# V1_4.net
KiCad netlist of a schematic drawn in Altium Designer
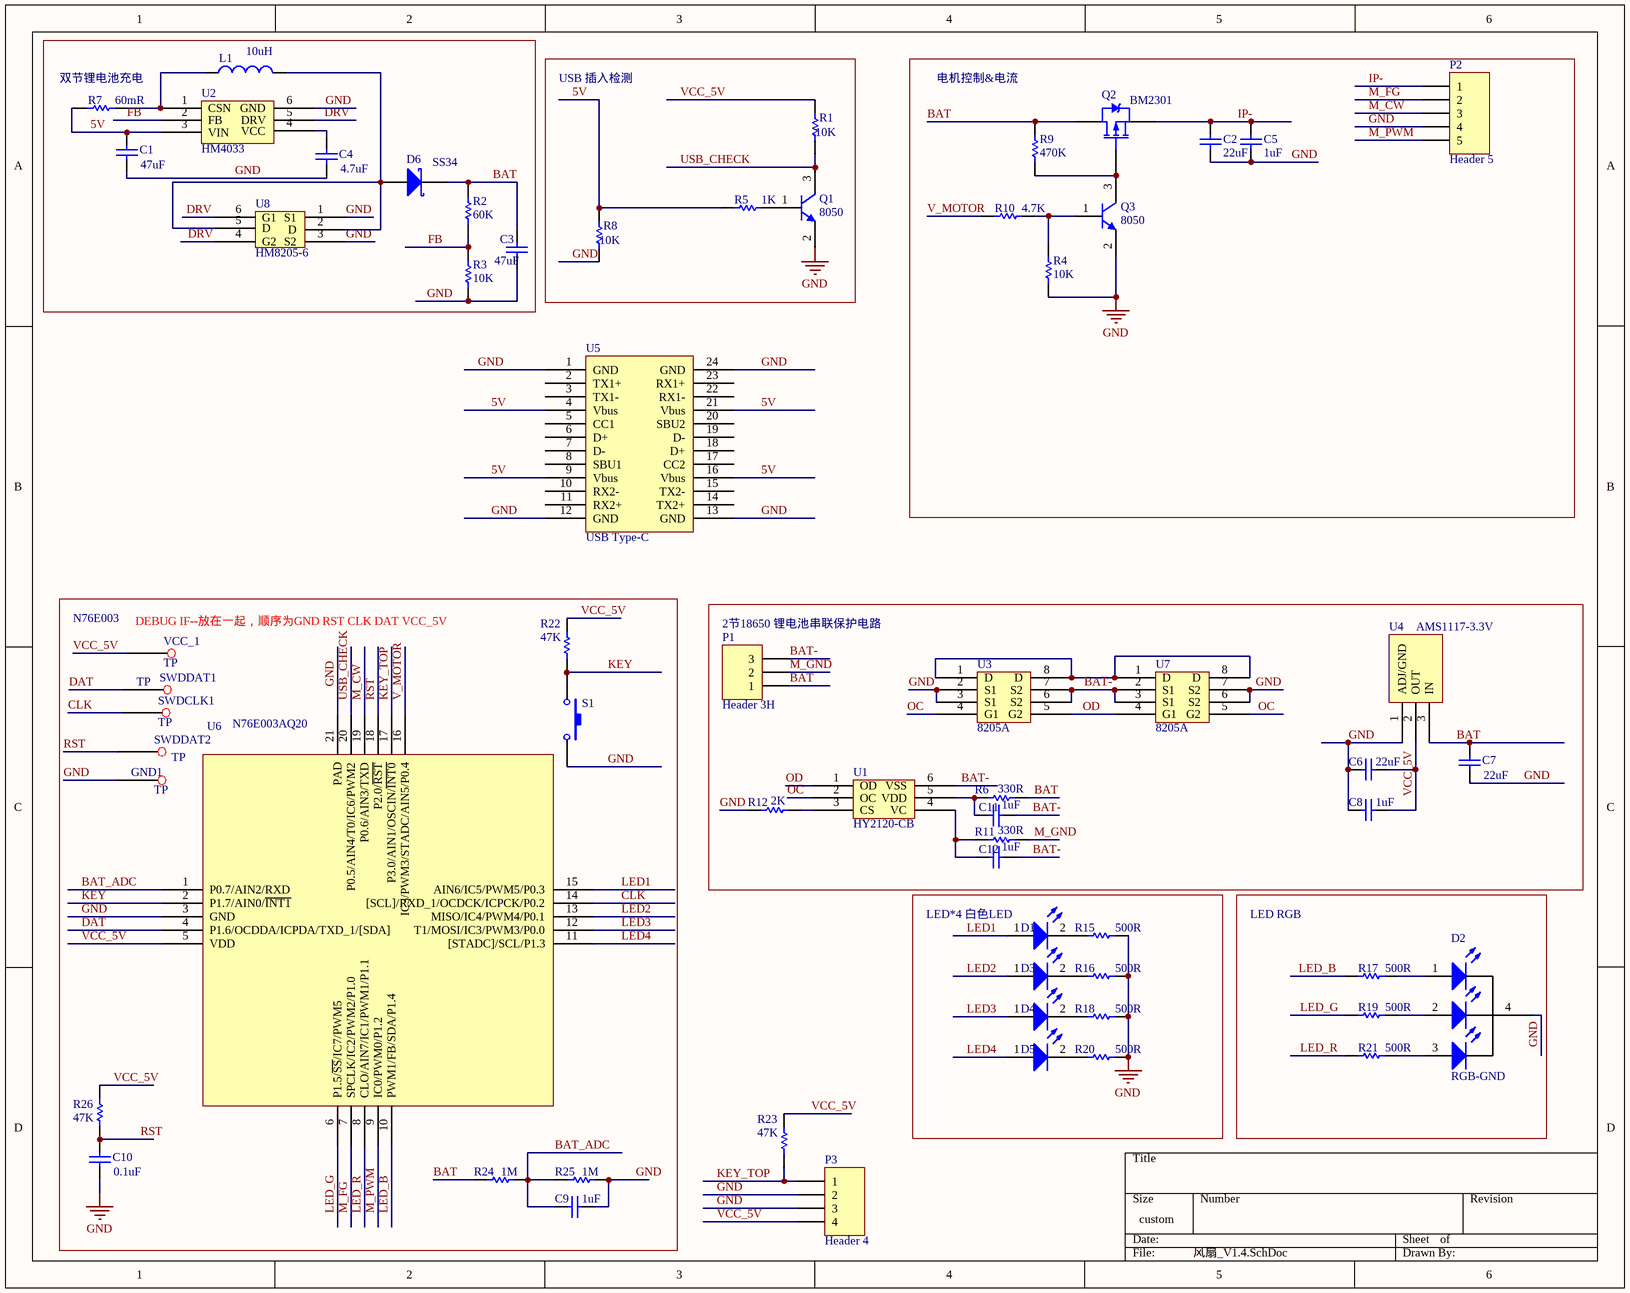
[diagram p0: 风扇_V1.4.SchDoc]

(export (version "E")
  (design (tool "Eeschema 10.0.6"))
  (components
    (comp (ref "C1")
      (value "47uF")
      (footprint "C-0603")
      (description "Capacitor")
      (fields (field (name "PUBLISHER") "Altium Limited"))
      (libsource (lib "Miscellaneous Devices") (part "Cap"))
    )
    (comp (ref "C2")
      (value "22uF")
      (footprint "C-0603")
      (description "Capacitor")
      (fields (field (name "PUBLISHER") "Altium Limited"))
      (libsource (lib "Miscellaneous Devices") (part "Cap"))
    )
    (comp (ref "C3")
      (value "47uF")
      (footprint "C-0603")
      (description "Capacitor")
      (fields (field (name "PUBLISHER") "Altium Limited"))
      (libsource (lib "Miscellaneous Devices") (part "Cap"))
    )
    (comp (ref "C4")
      (value "4.7uF")
      (footprint "C-0402")
      (description "Capacitor")
      (fields (field (name "PUBLISHER") "Altium Limited"))
      (libsource (lib "Miscellaneous Devices") (part "Cap"))
    )
    (comp (ref "C5")
      (value "1uF")
      (footprint "C-0402")
      (description "Capacitor")
      (fields (field (name "PUBLISHER") "Altium Limited"))
      (libsource (lib "Miscellaneous Devices") (part "Cap"))
    )
    (comp (ref "C6")
      (value "22uF")
      (footprint "C-0603")
      (description "Capacitor")
      (fields (field (name "PUBLISHER") "Altium Limited"))
      (libsource (lib "Miscellaneous Devices") (part "Cap"))
    )
    (comp (ref "C7")
      (value "22uF")
      (footprint "C-0603")
      (description "Capacitor")
      (fields (field (name "PUBLISHER") "Altium Limited"))
      (libsource (lib "Miscellaneous Devices") (part "Cap"))
    )
    (comp (ref "C8")
      (value "1uF")
      (footprint "C-0402")
      (description "Capacitor")
      (fields (field (name "PUBLISHER") "Altium Limited"))
      (libsource (lib "Miscellaneous Devices") (part "Cap"))
    )
    (comp (ref "C9")
      (value "1uF")
      (footprint "C-0402")
      (description "Capacitor")
      (fields (field (name "PUBLISHER") "Altium Limited"))
      (libsource (lib "Miscellaneous Devices") (part "Cap"))
    )
    (comp (ref "C10")
      (value "0.1uF")
      (footprint "C-0402")
      (description "Capacitor")
      (fields (field (name "PUBLISHER") "Altium Limited"))
      (libsource (lib "Miscellaneous Devices") (part "Cap"))
    )
    (comp (ref "C11")
      (value "1uF")
      (footprint "C-0402")
      (description "Capacitor")
      (fields (field (name "PUBLISHER") "Altium Limited"))
      (libsource (lib "Miscellaneous Devices") (part "Cap"))
    )
    (comp (ref "C12")
      (value "1uF")
      (footprint "C-0402")
      (description "Capacitor")
      (fields (field (name "PUBLISHER") "Altium Limited"))
      (libsource (lib "Miscellaneous Devices") (part "Cap"))
    )
    (comp (ref "D1")
      (value "LED0")
      (footprint "LED-0603")
      (description "Typical INFRARED GaAs LED")
      (fields (field (name "PUBLISHER") "Altium Limited"))
      (libsource (lib "Miscellaneous Devices") (part "LED0"))
    )
    (comp (ref "D2")
      (value "RGB-GND")
      (footprint "0603*2-LED")
      (libsource (lib "Others_IC_SCH_LIB") (part "RGB-GND"))
    )
    (comp (ref "D3")
      (value "LED0")
      (footprint "LED-0603")
      (description "Typical INFRARED GaAs LED")
      (fields (field (name "PUBLISHER") "Altium Limited"))
      (libsource (lib "Miscellaneous Devices") (part "LED0"))
    )
    (comp (ref "D4")
      (value "LED0")
      (footprint "LED-0603")
      (description "Typical INFRARED GaAs LED")
      (fields (field (name "PUBLISHER") "Altium Limited"))
      (libsource (lib "Miscellaneous Devices") (part "LED0"))
    )
    (comp (ref "D5")
      (value "LED0")
      (footprint "LED-0603")
      (description "Typical INFRARED GaAs LED")
      (fields (field (name "PUBLISHER") "Altium Limited"))
      (libsource (lib "Miscellaneous Devices") (part "LED0"))
    )
    (comp (ref "D6")
      (value "SS34")
      (footprint "HM4033 V1.0:DSMD")
      (description "Schottky Rectifier")
      (fields (field (name "PUBLISHER") "Altium Limited"))
      (libsource (lib "Miscellaneous Devices") (part "Diode 10TQ035"))
    )
    (comp (ref "GND1") (value "TP") (footprint "TP-1.5") (libsource (lib "Others_IC_SCH_LIB") (part "TP")))
    (comp (ref "L1")
      (value "10uH")
      (footprint "L-SMD")
      (description "Inductor")
      (fields (field (name "PUBLISHER") "Altium Limited"))
      (libsource (lib "Miscellaneous Devices") (part "Inductor"))
    )
    (comp (ref "P1")
      (value "Header 3H")
      (footprint "HED1X3")
      (description "Header, 3-Pin, Right Angle")
      (fields (field (name "PUBLISHER") "Altium Limited"))
      (libsource (lib "Miscellaneous Connectors") (part "Header 3H"))
    )
    (comp (ref "P2")
      (value "Header 5")
      (footprint "HDR1X5")
      (description "Header, 5-Pin")
      (fields (field (name "PUBLISHER") "Altium Limited"))
      (libsource (lib "Miscellaneous Connectors") (part "Header 5"))
    )
    (comp (ref "P3")
      (value "Header 4")
      (footprint "HDR1X4")
      (description "Header, 4-Pin")
      (fields (field (name "PUBLISHER") "Altium Limited"))
      (libsource (lib "Miscellaneous Connectors") (part "Header 4"))
    )
    (comp (ref "Q1")
      (value "8050")
      (footprint "SOT-23")
      (description "NPN Bipolar Transistor")
      (fields (field (name "PUBLISHER") "Altium Limited"))
      (libsource (lib "Miscellaneous Devices") (part "NPN"))
    )
    (comp (ref "Q2")
      (value "BM2301")
      (footprint "SOT-23")
      (description "P-Channel Power MOSFET")
      (fields (field (name "PUBLISHER") "Altium Limited"))
      (libsource (lib "Miscellaneous Devices") (part "PMOS-2"))
    )
    (comp (ref "Q3")
      (value "8050")
      (footprint "SOT-23")
      (description "NPN Bipolar Transistor")
      (fields (field (name "PUBLISHER") "Altium Limited"))
      (libsource (lib "Miscellaneous Devices") (part "NPN"))
    )
    (comp (ref "R1")
      (value "10K")
      (footprint "R-0402")
      (description "Resistor")
      (fields (field (name "PUBLISHER") "Altium Limited"))
      (libsource (lib "Miscellaneous Devices") (part "Res1"))
    )
    (comp (ref "R2")
      (value "60K")
      (footprint "R-0402")
      (description "Resistor")
      (fields (field (name "PUBLISHER") "Altium Limited"))
      (libsource (lib "Miscellaneous Devices") (part "Res1"))
    )
    (comp (ref "R3")
      (value "10K")
      (footprint "R-0402")
      (description "Resistor")
      (fields (field (name "PUBLISHER") "Altium Limited"))
      (libsource (lib "Miscellaneous Devices") (part "Res1"))
    )
    (comp (ref "R4")
      (value "10K")
      (footprint "R-0402")
      (description "Resistor")
      (fields (field (name "PUBLISHER") "Altium Limited"))
      (libsource (lib "Miscellaneous Devices") (part "Res1"))
    )
    (comp (ref "R5")
      (value "1K")
      (footprint "R-0402")
      (description "Resistor")
      (fields (field (name "PUBLISHER") "Altium Limited"))
      (libsource (lib "Miscellaneous Devices") (part "Res1"))
    )
    (comp (ref "R6")
      (value "330R")
      (footprint "R-0402")
      (description "Resistor")
      (fields (field (name "PUBLISHER") "Altium Limited"))
      (libsource (lib "Miscellaneous Devices") (part "Res1"))
    )
    (comp (ref "R7")
      (value "60mR")
      (footprint "R-0402")
      (description "Resistor")
      (fields (field (name "PUBLISHER") "Altium Limited"))
      (libsource (lib "Miscellaneous Devices") (part "Res1"))
    )
    (comp (ref "R8")
      (value "10K")
      (footprint "R-0402")
      (description "Resistor")
      (fields (field (name "PUBLISHER") "Altium Limited"))
      (libsource (lib "Miscellaneous Devices") (part "Res1"))
    )
    (comp (ref "R9")
      (value "470K")
      (footprint "R-0402")
      (description "Resistor")
      (fields (field (name "PUBLISHER") "Altium Limited"))
      (libsource (lib "Miscellaneous Devices") (part "Res1"))
    )
    (comp (ref "R10")
      (value "4.7K")
      (footprint "R-0402")
      (description "Resistor")
      (fields (field (name "PUBLISHER") "Altium Limited"))
      (libsource (lib "Miscellaneous Devices") (part "Res1"))
    )
    (comp (ref "R11")
      (value "330R")
      (footprint "R-0402")
      (description "Resistor")
      (fields (field (name "PUBLISHER") "Altium Limited"))
      (libsource (lib "Miscellaneous Devices") (part "Res1"))
    )
    (comp (ref "R12")
      (value "2K")
      (footprint "R-0402")
      (description "Resistor")
      (fields (field (name "PUBLISHER") "Altium Limited"))
      (libsource (lib "Miscellaneous Devices") (part "Res1"))
    )
    (comp (ref "R15")
      (value "500R")
      (footprint "R-0402")
      (description "Resistor")
      (fields (field (name "PUBLISHER") "Altium Limited"))
      (libsource (lib "Miscellaneous Devices") (part "Res1"))
    )
    (comp (ref "R16")
      (value "500R")
      (footprint "R-0402")
      (description "Resistor")
      (fields (field (name "PUBLISHER") "Altium Limited"))
      (libsource (lib "Miscellaneous Devices") (part "Res1"))
    )
    (comp (ref "R17")
      (value "500R")
      (footprint "R-0402")
      (description "Resistor")
      (fields (field (name "PUBLISHER") "Altium Limited"))
      (libsource (lib "Miscellaneous Devices") (part "Res1"))
    )
    (comp (ref "R18")
      (value "500R")
      (footprint "R-0402")
      (description "Resistor")
      (fields (field (name "PUBLISHER") "Altium Limited"))
      (libsource (lib "Miscellaneous Devices") (part "Res1"))
    )
    (comp (ref "R19")
      (value "500R")
      (footprint "R-0402")
      (description "Resistor")
      (fields (field (name "PUBLISHER") "Altium Limited"))
      (libsource (lib "Miscellaneous Devices") (part "Res1"))
    )
    (comp (ref "R20")
      (value "500R")
      (footprint "R-0402")
      (description "Resistor")
      (fields (field (name "PUBLISHER") "Altium Limited"))
      (libsource (lib "Miscellaneous Devices") (part "Res1"))
    )
    (comp (ref "R21")
      (value "500R")
      (footprint "R-0402")
      (description "Resistor")
      (fields (field (name "PUBLISHER") "Altium Limited"))
      (libsource (lib "Miscellaneous Devices") (part "Res1"))
    )
    (comp (ref "R22")
      (value "47K")
      (footprint "R-0402")
      (description "Resistor")
      (fields (field (name "PUBLISHER") "Altium Limited"))
      (libsource (lib "Miscellaneous Devices") (part "Res1"))
    )
    (comp (ref "R23")
      (value "47K")
      (footprint "R-0402")
      (description "Resistor")
      (fields (field (name "PUBLISHER") "Altium Limited"))
      (libsource (lib "Miscellaneous Devices") (part "Res1"))
    )
    (comp (ref "R24")
      (value "1M")
      (footprint "R-0402")
      (description "Resistor")
      (fields (field (name "PUBLISHER") "Altium Limited"))
      (libsource (lib "Miscellaneous Devices") (part "Res1"))
    )
    (comp (ref "R25")
      (value "1M")
      (footprint "R-0402")
      (description "Resistor")
      (fields (field (name "PUBLISHER") "Altium Limited"))
      (libsource (lib "Miscellaneous Devices") (part "Res1"))
    )
    (comp (ref "R26")
      (value "47K")
      (footprint "R-0402")
      (description "Resistor")
      (fields (field (name "PUBLISHER") "Altium Limited"))
      (libsource (lib "Miscellaneous Devices") (part "Res1"))
    )
    (comp (ref "S1")
      (value "SW-PB")
      (footprint "SW-6*6*4.3")
      (description "Switch")
      (fields (field (name "PUBLISHER") "Altium Limited"))
      (libsource (lib "Miscellaneous Devices") (part "SW-PB"))
    )
    (comp (ref "SWDCLK1") (value "TP") (footprint "TP-1.5") (libsource (lib "Others_IC_SCH_LIB") (part "TP")))
    (comp (ref "SWDDAT1") (value "TP") (footprint "TP-1.5") (libsource (lib "Others_IC_SCH_LIB") (part "TP")))
    (comp (ref "SWDDAT2") (value "TP") (footprint "TP-1.5") (libsource (lib "Others_IC_SCH_LIB") (part "TP")))
    (comp (ref "U1")
      (value "HY2120-CB")
      (footprint "SOT-23-6L")
      (libsource (lib "Others_IC_SCH_LIB") (part "HY2120"))
    )
    (comp (ref "U2")
      (value "HM4033")
      (footprint "SOT-23-6L")
      (libsource (lib "Others_IC_SCH_LIB") (part "HM4033"))
    )
    (comp (ref "U3")
      (value "8205A")
      (footprint "TSSOP8")
      (libsource (lib "Others_IC_SCH_LIB") (part "8205A"))
    )
    (comp (ref "U4")
      (value "AMS1117-3.3V")
      (footprint "SOT-223")
      (libsource (lib "Others_IC_SCH_LIB") (part "AMS1117"))
    )
    (comp (ref "U5")
      (value "USB Type-C")
      (footprint "USB-type C")
      (libsource (lib "Others_IC_SCH_LIB") (part "USB Type-C"))
    )
    (comp (ref "U6")
      (value "N76E003AQ20")
      (footprint "QFN-20 0.4mm")
      (libsource (lib "Others_IC_SCH_LIB") (part "N76E003AQ20"))
    )
    (comp (ref "U7")
      (value "8205A")
      (footprint "TSSOP8")
      (libsource (lib "Others_IC_SCH_LIB") (part "8205A"))
    )
    (comp (ref "U8")
      (value "HM8205-6")
      (footprint "SOT-23-6L")
      (libsource (lib "Others_IC_SCH_LIB") (part "HM8205-6"))
    )
    (comp (ref "VCC_1") (value "TP") (footprint "TP-1.5") (libsource (lib "Others_IC_SCH_LIB") (part "TP")))
  )
  (nets
    (net (code "1") (name "/5V") (class "Default")
      (node (ref "C1") (pin "1") (pinfunction "1_1") (pintype "passive"))
      (node (ref "R5") (pin "1") (pinfunction "1_1") (pintype "passive"))
      (node (ref "R7") (pin "2") (pinfunction "2_2") (pintype "passive"))
      (node (ref "R8") (pin "1") (pinfunction "1_1") (pintype "passive"))
      (node (ref "U2") (pin "3") (pinfunction "VIN_3") (pintype "passive"))
      (node (ref "U5") (pin "16") (pinfunction "Vbus_16") (pintype "passive"))
      (node (ref "U5") (pin "21") (pinfunction "Vbus_21") (pintype "passive"))
      (node (ref "U5") (pin "4") (pinfunction "Vbus_4") (pintype "passive"))
      (node (ref "U5") (pin "9") (pinfunction "Vbus_9") (pintype "passive"))
    )
    (net (code "2") (name "/BAT") (class "Default")
      (node (ref "C3") (pin "2") (pinfunction "2_2") (pintype "passive"))
      (node (ref "C7") (pin "2") (pinfunction "2_2") (pintype "passive"))
      (node (ref "D6") (pin "1") (pinfunction "K_1") (pintype "passive"))
      (node (ref "P1") (pin "1") (pinfunction "1_1") (pintype "passive"))
      (node (ref "Q2") (pin "2") (pinfunction "D_2") (pintype "passive"))
      (node (ref "R2") (pin "1") (pinfunction "1_1") (pintype "passive"))
      (node (ref "R24") (pin "1") (pinfunction "1_1") (pintype "passive"))
      (node (ref "R6") (pin "2") (pinfunction "2_2") (pintype "passive"))
      (node (ref "R9") (pin "2") (pinfunction "2_2") (pintype "passive"))
      (node (ref "U4") (pin "3") (pinfunction "IN_3") (pintype "passive"))
    )
    (net (code "3") (name "/BAT-") (class "Default")
      (node (ref "C11") (pin "1") (pinfunction "1_1") (pintype "passive"))
      (node (ref "C12") (pin "1") (pinfunction "1_1") (pintype "passive"))
      (node (ref "P1") (pin "3") (pinfunction "3_3") (pintype "passive"))
      (node (ref "U1") (pin "6") (pinfunction "VSS_6") (pintype "passive"))
      (node (ref "U3") (pin "6") (pinfunction "S2_6") (pintype "passive"))
      (node (ref "U3") (pin "7") (pinfunction "S2_7") (pintype "passive"))
      (node (ref "U7") (pin "2") (pinfunction "S1_2") (pintype "passive"))
      (node (ref "U7") (pin "3") (pinfunction "S1_3") (pintype "passive"))
    )
    (net (code "4") (name "/BAT_ADC") (class "Default")
      (node (ref "C9") (pin "2") (pinfunction "2_2") (pintype "passive"))
      (node (ref "R24") (pin "2") (pinfunction "2_2") (pintype "passive"))
      (node (ref "R25") (pin "1") (pinfunction "1_1") (pintype "passive"))
      (node (ref "U6") (pin "1") (pinfunction "P0.7/AIN2/RXD_1") (pintype "passive"))
    )
    (net (code "5") (name "/CLK") (class "Default")
      (node (ref "SWDCLK1") (pin "1") (pinfunction "1_1") (pintype "passive"))
      (node (ref "U6") (pin "14") (pinfunction "[SCL]/RXD_1/OCDCK/ICPCK/P0.2_14") (pintype "passive"))
    )
    (net (code "6") (name "/DAT") (class "Default")
      (node (ref "SWDDAT1") (pin "1") (pinfunction "1_1") (pintype "passive"))
      (node (ref "U6") (pin "4") (pinfunction "P1.6/OCDDA/ICPDA/TXD_1/[SDA]_4") (pintype "passive"))
    )
    (net (code "7") (name "/DRV") (class "Default")
      (node (ref "U2") (pin "5") (pinfunction "DRV_5") (pintype "passive"))
      (node (ref "U8") (pin "4") (pinfunction "G2_4") (pintype "passive"))
      (node (ref "U8") (pin "6") (pinfunction "G1_6") (pintype "passive"))
    )
    (net (code "8") (name "/FB") (class "Default")
      (node (ref "R2") (pin "2") (pinfunction "2_2") (pintype "passive"))
      (node (ref "R3") (pin "1") (pinfunction "1_1") (pintype "passive"))
      (node (ref "U2") (pin "2") (pinfunction "FB_2") (pintype "passive"))
    )
    (net (code "9") (name "/IP-") (class "Default")
      (node (ref "C2") (pin "2") (pinfunction "2_2") (pintype "passive"))
      (node (ref "C5") (pin "2") (pinfunction "2_2") (pintype "passive"))
      (node (ref "P2") (pin "1") (pinfunction "1_1") (pintype "passive"))
      (node (ref "Q2") (pin "3") (pinfunction "S_3") (pintype "passive"))
    )
    (net (code "10") (name "/KEY") (class "Default")
      (node (ref "R22") (pin "1") (pinfunction "1_1") (pintype "passive"))
      (node (ref "S1") (pin "1") (pinfunction "1_1") (pintype "passive"))
      (node (ref "U6") (pin "2") (pinfunction "P1.7/AIN0/~{INT1}_2") (pintype "passive"))
    )
    (net (code "11") (name "/KEY_TOP") (class "Default")
      (node (ref "P3") (pin "1") (pinfunction "1_1") (pintype "passive"))
      (node (ref "R23") (pin "1") (pinfunction "1_1") (pintype "passive"))
      (node (ref "U6") (pin "17") (pinfunction "P3.0/AIN1/OSCIN/~{INT0}_17") (pintype "passive"))
    )
    (net (code "12") (name "/LED1") (class "Default")
      (node (ref "D1") (pin "1") (pinfunction "A_1") (pintype "passive"))
      (node (ref "U6") (pin "15") (pinfunction "AIN6/IC5/PWM5/P0.3_15") (pintype "passive"))
    )
    (net (code "13") (name "/LED2") (class "Default")
      (node (ref "D3") (pin "1") (pinfunction "A_1") (pintype "passive"))
      (node (ref "U6") (pin "13") (pinfunction "MISO/IC4/PWM4/P0.1_13") (pintype "passive"))
    )
    (net (code "14") (name "/LED3") (class "Default")
      (node (ref "D4") (pin "1") (pinfunction "A_1") (pintype "passive"))
      (node (ref "U6") (pin "12") (pinfunction "T1/MOSI/IC3/PWM3/P0.0_12") (pintype "passive"))
    )
    (net (code "15") (name "/LED4") (class "Default")
      (node (ref "D5") (pin "1") (pinfunction "A_1") (pintype "passive"))
      (node (ref "U6") (pin "11") (pinfunction "[STADC]/SCL/P1.3_11") (pintype "passive"))
    )
    (net (code "16") (name "/LED_B") (class "Default")
      (node (ref "R17") (pin "1") (pinfunction "1_1") (pintype "passive"))
      (node (ref "U6") (pin "10") (pinfunction "PWM1/FB/SDA/P1.4_10") (pintype "passive"))
    )
    (net (code "17") (name "/LED_G") (class "Default")
      (node (ref "R19") (pin "1") (pinfunction "1_1") (pintype "passive"))
      (node (ref "U6") (pin "6") (pinfunction "P1.5/~{SS}/IC7/PWM5_6") (pintype "passive"))
    )
    (net (code "18") (name "/LED_R") (class "Default")
      (node (ref "R21") (pin "1") (pinfunction "1_1") (pintype "passive"))
      (node (ref "U6") (pin "8") (pinfunction "CLO/AIN7/IC1/PWM1/P1.1_8") (pintype "passive"))
    )
    (net (code "19") (name "/M_CW") (class "Default")
      (node (ref "P2") (pin "3") (pinfunction "3_3") (pintype "passive"))
      (node (ref "U6") (pin "19") (pinfunction "P0.6/AIN3/TXD_19") (pintype "passive"))
    )
    (net (code "20") (name "/M_FG") (class "Default")
      (node (ref "P2") (pin "2") (pinfunction "2_2") (pintype "passive"))
      (node (ref "U6") (pin "7") (pinfunction "SPCLK/IC2/PWM2/P1.0_7") (pintype "passive"))
    )
    (net (code "21") (name "/M_GND") (class "Default")
      (node (ref "P1") (pin "2") (pinfunction "2_2") (pintype "passive"))
      (node (ref "R11") (pin "2") (pinfunction "2_2") (pintype "passive"))
    )
    (net (code "22") (name "/M_PWM") (class "Default")
      (node (ref "P2") (pin "5") (pinfunction "5_5") (pintype "passive"))
      (node (ref "U6") (pin "9") (pinfunction "IC0/PWM0/P1.2_9") (pintype "passive"))
    )
    (net (code "23") (name "/OC") (class "Default")
      (node (ref "U1") (pin "2") (pinfunction "OC_2") (pintype "passive"))
      (node (ref "U3") (pin "4") (pinfunction "G1_4") (pintype "passive"))
      (node (ref "U7") (pin "5") (pinfunction "G2_5") (pintype "passive"))
    )
    (net (code "24") (name "/OD") (class "Default")
      (node (ref "U1") (pin "1") (pinfunction "OD_1") (pintype "passive"))
      (node (ref "U3") (pin "5") (pinfunction "G2_5") (pintype "passive"))
      (node (ref "U7") (pin "4") (pinfunction "G1_4") (pintype "passive"))
    )
    (net (code "25") (name "/RST") (class "Default")
      (node (ref "C10") (pin "2") (pinfunction "2_2") (pintype "passive"))
      (node (ref "R26") (pin "1") (pinfunction "1_1") (pintype "passive"))
      (node (ref "SWDDAT2") (pin "1") (pinfunction "1_1") (pintype "passive"))
      (node (ref "U6") (pin "18") (pinfunction "P2.0/~{RST}_18") (pintype "passive"))
    )
    (net (code "26") (name "/USB_CHECK") (class "Default")
      (node (ref "Q1") (pin "3") (pinfunction "C_3") (pintype "passive"))
      (node (ref "R1") (pin "1") (pinfunction "1_1") (pintype "passive"))
      (node (ref "U6") (pin "20") (pinfunction "P0.5/AIN4/T0/IC6/PWM2_20") (pintype "passive"))
    )
    (net (code "27") (name "/VCC_5V") (class "Default")
      (node (ref "C6") (pin "2") (pinfunction "2_2") (pintype "passive"))
      (node (ref "C8") (pin "2") (pinfunction "2_2") (pintype "passive"))
      (node (ref "P3") (pin "4") (pinfunction "4_4") (pintype "passive"))
      (node (ref "R1") (pin "2") (pinfunction "2_2") (pintype "passive"))
      (node (ref "R22") (pin "2") (pinfunction "2_2") (pintype "passive"))
      (node (ref "R23") (pin "2") (pinfunction "2_2") (pintype "passive"))
      (node (ref "R26") (pin "2") (pinfunction "2_2") (pintype "passive"))
      (node (ref "U4") (pin "2") (pinfunction "OUT_2") (pintype "passive"))
      (node (ref "U6") (pin "5") (pinfunction "VDD_5") (pintype "passive"))
      (node (ref "VCC_1") (pin "1") (pinfunction "1_1") (pintype "passive"))
    )
    (net (code "28") (name "/V_MOTOR") (class "Default")
      (node (ref "R10") (pin "1") (pinfunction "1_1") (pintype "passive"))
      (node (ref "U6") (pin "16") (pinfunction "IC3/PWM3/STADC/AIN5/P0.4_16") (pintype "passive"))
    )
    (net (code "29") (name "GND") (class "Default")
      (node (ref "C1") (pin "2") (pinfunction "2_2") (pintype "passive"))
      (node (ref "C10") (pin "1") (pinfunction "1_1") (pintype "passive"))
      (node (ref "C2") (pin "1") (pinfunction "1_1") (pintype "passive"))
      (node (ref "C3") (pin "1") (pinfunction "1_1") (pintype "passive"))
      (node (ref "C4") (pin "2") (pinfunction "2_2") (pintype "passive"))
      (node (ref "C5") (pin "1") (pinfunction "1_1") (pintype "passive"))
      (node (ref "C6") (pin "1") (pinfunction "1_1") (pintype "passive"))
      (node (ref "C7") (pin "1") (pinfunction "1_1") (pintype "passive"))
      (node (ref "C8") (pin "1") (pinfunction "1_1") (pintype "passive"))
      (node (ref "C9") (pin "1") (pinfunction "1_1") (pintype "passive"))
      (node (ref "D2") (pin "4") (pinfunction "4_4") (pintype "passive"))
      (node (ref "GND1") (pin "1") (pinfunction "1_1") (pintype "passive"))
      (node (ref "P2") (pin "4") (pinfunction "4_4") (pintype "passive"))
      (node (ref "P3") (pin "2") (pinfunction "2_2") (pintype "passive"))
      (node (ref "P3") (pin "3") (pinfunction "3_3") (pintype "passive"))
      (node (ref "Q1") (pin "2") (pinfunction "E_2") (pintype "passive"))
      (node (ref "Q3") (pin "2") (pinfunction "E_2") (pintype "passive"))
      (node (ref "R12") (pin "1") (pinfunction "1_1") (pintype "passive"))
      (node (ref "R15") (pin "2") (pinfunction "2_2") (pintype "passive"))
      (node (ref "R16") (pin "2") (pinfunction "2_2") (pintype "passive"))
      (node (ref "R18") (pin "2") (pinfunction "2_2") (pintype "passive"))
      (node (ref "R20") (pin "2") (pinfunction "2_2") (pintype "passive"))
      (node (ref "R25") (pin "2") (pinfunction "2_2") (pintype "passive"))
      (node (ref "R3") (pin "2") (pinfunction "2_2") (pintype "passive"))
      (node (ref "R4") (pin "1") (pinfunction "1_1") (pintype "passive"))
      (node (ref "R8") (pin "2") (pinfunction "2_2") (pintype "passive"))
      (node (ref "S1") (pin "2") (pinfunction "2_2") (pintype "passive"))
      (node (ref "U2") (pin "6") (pinfunction "GND_6") (pintype "passive"))
      (node (ref "U3") (pin "2") (pinfunction "S1_2") (pintype "passive"))
      (node (ref "U3") (pin "3") (pinfunction "S1_3") (pintype "passive"))
      (node (ref "U4") (pin "1") (pinfunction "ADJ/GND_1") (pintype "passive"))
      (node (ref "U5") (pin "1") (pinfunction "GND_1") (pintype "passive"))
      (node (ref "U5") (pin "12") (pinfunction "GND_12") (pintype "passive"))
      (node (ref "U5") (pin "13") (pinfunction "GND_13") (pintype "passive"))
      (node (ref "U5") (pin "24") (pinfunction "GND_24") (pintype "passive"))
      (node (ref "U6") (pin "21") (pinfunction "PAD_21") (pintype "passive"))
      (node (ref "U6") (pin "3") (pinfunction "GND_3") (pintype "passive"))
      (node (ref "U7") (pin "6") (pinfunction "S2_6") (pintype "passive"))
      (node (ref "U7") (pin "7") (pinfunction "S2_7") (pintype "passive"))
      (node (ref "U8") (pin "1") (pinfunction "S1_1") (pintype "passive"))
      (node (ref "U8") (pin "3") (pinfunction "S2_3") (pintype "passive"))
    )
    (net (code "30") (name "Net-(D1-K)") (class "Default")
      (node (ref "D1") (pin "2") (pinfunction "K_2") (pintype "passive"))
      (node (ref "R15") (pin "1") (pinfunction "1_1") (pintype "passive"))
    )
    (net (code "31") (name "Net-(D2-Pad1)") (class "Default")
      (node (ref "D2") (pin "1") (pinfunction "1_1") (pintype "passive"))
      (node (ref "R17") (pin "2") (pinfunction "2_2") (pintype "passive"))
    )
    (net (code "32") (name "Net-(D2-Pad2)") (class "Default")
      (node (ref "D2") (pin "2") (pinfunction "2_2") (pintype "passive"))
      (node (ref "R19") (pin "2") (pinfunction "2_2") (pintype "passive"))
    )
    (net (code "33") (name "Net-(D2-Pad3)") (class "Default")
      (node (ref "D2") (pin "3") (pinfunction "3_3") (pintype "passive"))
      (node (ref "R21") (pin "2") (pinfunction "2_2") (pintype "passive"))
    )
    (net (code "34") (name "Net-(D3-K)") (class "Default")
      (node (ref "D3") (pin "2") (pinfunction "K_2") (pintype "passive"))
      (node (ref "R16") (pin "1") (pinfunction "1_1") (pintype "passive"))
    )
    (net (code "35") (name "Net-(D4-K)") (class "Default")
      (node (ref "D4") (pin "2") (pinfunction "K_2") (pintype "passive"))
      (node (ref "R18") (pin "1") (pinfunction "1_1") (pintype "passive"))
    )
    (net (code "36") (name "Net-(D5-K)") (class "Default")
      (node (ref "D5") (pin "2") (pinfunction "K_2") (pintype "passive"))
      (node (ref "R20") (pin "1") (pinfunction "1_1") (pintype "passive"))
    )
    (net (code "37") (name "Net-(D6-A)") (class "Default")
      (node (ref "D6") (pin "3") (pinfunction "A_3") (pintype "passive"))
      (node (ref "L1") (pin "2") (pinfunction "2_2") (pintype "passive"))
      (node (ref "U8") (pin "2") (pinfunction "D_2") (pintype "passive"))
      (node (ref "U8") (pin "5") (pinfunction "D_5") (pintype "passive"))
    )
    (net (code "38") (name "Net-(Q1-B)") (class "Default")
      (node (ref "Q1") (pin "1") (pinfunction "B_1") (pintype "passive"))
      (node (ref "R5") (pin "2") (pinfunction "2_2") (pintype "passive"))
    )
    (net (code "39") (name "Net-(Q2-G)") (class "Default")
      (node (ref "Q2") (pin "1") (pinfunction "G_1") (pintype "passive"))
      (node (ref "Q3") (pin "3") (pinfunction "C_3") (pintype "passive"))
      (node (ref "R9") (pin "1") (pinfunction "1_1") (pintype "passive"))
    )
    (net (code "40") (name "Net-(Q3-B)") (class "Default")
      (node (ref "Q3") (pin "1") (pinfunction "B_1") (pintype "passive"))
      (node (ref "R10") (pin "2") (pinfunction "2_2") (pintype "passive"))
      (node (ref "R4") (pin "2") (pinfunction "2_2") (pintype "passive"))
    )
    (net (code "41") (name "Net-(U1-CS)") (class "Default")
      (node (ref "R12") (pin "2") (pinfunction "2_2") (pintype "passive"))
      (node (ref "U1") (pin "3") (pinfunction "CS_3") (pintype "passive"))
    )
    (net (code "42") (name "Net-(U1-VC)") (class "Default")
      (node (ref "C12") (pin "2") (pinfunction "2_2") (pintype "passive"))
      (node (ref "R11") (pin "1") (pinfunction "1_1") (pintype "passive"))
      (node (ref "U1") (pin "4") (pinfunction "VC_4") (pintype "passive"))
    )
    (net (code "43") (name "Net-(U1-VDD)") (class "Default")
      (node (ref "C11") (pin "2") (pinfunction "2_2") (pintype "passive"))
      (node (ref "R6") (pin "1") (pinfunction "1_1") (pintype "passive"))
      (node (ref "U1") (pin "5") (pinfunction "VDD_5") (pintype "passive"))
    )
    (net (code "44") (name "Net-(U2-CSN)") (class "Default")
      (node (ref "L1") (pin "1") (pinfunction "1_1") (pintype "passive"))
      (node (ref "R7") (pin "1") (pinfunction "1_1") (pintype "passive"))
      (node (ref "U2") (pin "1") (pinfunction "CSN_1") (pintype "passive"))
    )
    (net (code "45") (name "Net-(U2-VCC)") (class "Default")
      (node (ref "C4") (pin "1") (pinfunction "1_1") (pintype "passive"))
      (node (ref "U2") (pin "4") (pinfunction "VCC_4") (pintype "passive"))
    )
    (net (code "46") (name "Net-(U3-D-Pad1)") (class "Default")
      (node (ref "U3") (pin "1") (pinfunction "D_1") (pintype "passive"))
      (node (ref "U3") (pin "8") (pinfunction "D_8") (pintype "passive"))
      (node (ref "U7") (pin "1") (pinfunction "D_1") (pintype "passive"))
      (node (ref "U7") (pin "8") (pinfunction "D_8") (pintype "passive"))
    )
    (net (code "47") (name "unconnected-(U5-CC1-Pad5)") (class "Default")
      (node (ref "U5") (pin "5") (pinfunction "CC1_5") (pintype "passive"))
    )
    (net (code "48") (name "unconnected-(U5-CC2-Pad17)") (class "Default")
      (node (ref "U5") (pin "17") (pinfunction "CC2_17") (pintype "passive"))
    )
    (net (code "49") (name "unconnected-(U5-D+-Pad6)") (class "Default")
      (node (ref "U5") (pin "6") (pinfunction "D+_6") (pintype "passive"))
    )
    (net (code "50") (name "unconnected-(U5-D+-Pad18)") (class "Default")
      (node (ref "U5") (pin "18") (pinfunction "D+_18") (pintype "passive"))
    )
    (net (code "51") (name "unconnected-(U5-D--Pad7)") (class "Default")
      (node (ref "U5") (pin "7") (pinfunction "D-_7") (pintype "passive"))
    )
    (net (code "52") (name "unconnected-(U5-D--Pad19)") (class "Default")
      (node (ref "U5") (pin "19") (pinfunction "D-_19") (pintype "passive"))
    )
    (net (code "53") (name "unconnected-(U5-RX1+-Pad23)") (class "Default")
      (node (ref "U5") (pin "23") (pinfunction "RX1+_23") (pintype "passive"))
    )
    (net (code "54") (name "unconnected-(U5-RX1--Pad22)") (class "Default")
      (node (ref "U5") (pin "22") (pinfunction "RX1-_22") (pintype "passive"))
    )
    (net (code "55") (name "unconnected-(U5-RX2+-Pad11)") (class "Default")
      (node (ref "U5") (pin "11") (pinfunction "RX2+_11") (pintype "passive"))
    )
    (net (code "56") (name "unconnected-(U5-RX2--Pad10)") (class "Default")
      (node (ref "U5") (pin "10") (pinfunction "RX2-_10") (pintype "passive"))
    )
    (net (code "57") (name "unconnected-(U5-SBU1-Pad8)") (class "Default")
      (node (ref "U5") (pin "8") (pinfunction "SBU1_8") (pintype "passive"))
    )
    (net (code "58") (name "unconnected-(U5-SBU2-Pad20)") (class "Default")
      (node (ref "U5") (pin "20") (pinfunction "SBU2_20") (pintype "passive"))
    )
    (net (code "59") (name "unconnected-(U5-TX1+-Pad2)") (class "Default")
      (node (ref "U5") (pin "2") (pinfunction "TX1+_2") (pintype "passive"))
    )
    (net (code "60") (name "unconnected-(U5-TX1--Pad3)") (class "Default")
      (node (ref "U5") (pin "3") (pinfunction "TX1-_3") (pintype "passive"))
    )
    (net (code "61") (name "unconnected-(U5-TX2+-Pad14)") (class "Default")
      (node (ref "U5") (pin "14") (pinfunction "TX2+_14") (pintype "passive"))
    )
    (net (code "62") (name "unconnected-(U5-TX2--Pad15)") (class "Default")
      (node (ref "U5") (pin "15") (pinfunction "TX2-_15") (pintype "passive"))
    )
  )
)
